# HRT.net
KiCad netlist of a schematic drawn in Altium Designer
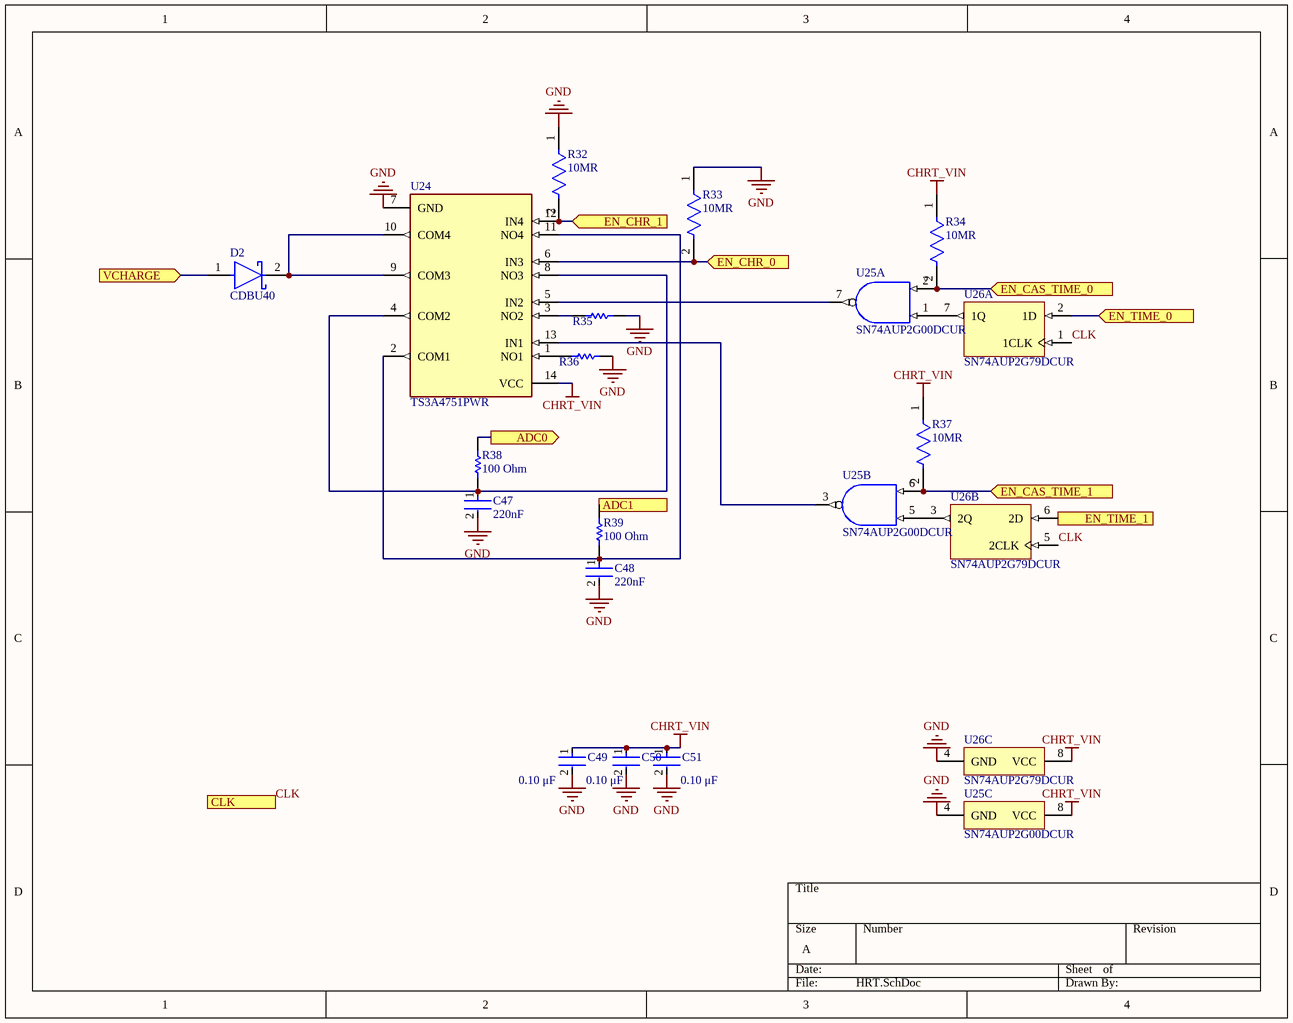
[diagram p0: HRT.SchDoc]

(export (version "E")
  (design (tool "Eeschema 10.0.6"))
  (components
    (comp (ref "C47")
      (value "GRM155R71C224KA12D")
      (footprint "FP-GRM155-0_05-IPC_C")
      (description "Chip Multilayer Ceramic Capacitors for General Purpose, 0402, 0.22uF, X7R, 15%, 10%, 16V")
      (fields
        (field (name "CAPACITANCE") "220nF")
        (field (name "VOLTAGE") "16V")
        (field (name "TOLERANCE") "10%")
      )
      (libsource (lib "Altium Content Vault") (part "02cd4be3c70576c341d710602a673aa"))
    )
    (comp (ref "C48")
      (value "GRM155R71C224KA12D")
      (footprint "FP-GRM155-0_05-IPC_C")
      (description "Chip Multilayer Ceramic Capacitors for General Purpose, 0402, 0.22uF, X7R, 15%, 10%, 16V")
      (fields
        (field (name "CAPACITANCE") "220nF")
        (field (name "VOLTAGE") "16V")
        (field (name "TOLERANCE") "10%")
      )
      (libsource (lib "Altium Content Vault") (part "02cd4be3c70576c341d710602a673aa"))
    )
    (comp (ref "C49")
      (value "C0402C104K8PACTU")
      (footprint "FP-C0402-BB-MFG")
      (description "CAP CER 0.1UF 10V X5R 0402")
      (fields
        (field (name "CAPACITANCE") "0.10 μF")
        (field (name "MANUFACTURER") "Kemet")
        (field (name "TOLERANCE") "0.1")
      )
      (libsource (lib "Altium Content Vault") (part "b4654b650e69147ec39a6b967a45e02"))
    )
    (comp (ref "C50")
      (value "C0402C104K8PACTU")
      (footprint "FP-C0402-BB-MFG")
      (description "CAP CER 0.1UF 10V X5R 0402")
      (fields
        (field (name "CAPACITANCE") "0.10 μF")
        (field (name "MANUFACTURER") "Kemet")
        (field (name "TOLERANCE") "0.1")
      )
      (libsource (lib "Altium Content Vault") (part "b4654b650e69147ec39a6b967a45e02"))
    )
    (comp (ref "C51")
      (value "C0402C104K8PACTU")
      (footprint "FP-C0402-BB-MFG")
      (description "CAP CER 0.1UF 10V X5R 0402")
      (fields
        (field (name "CAPACITANCE") "0.10 μF")
        (field (name "MANUFACTURER") "Kemet")
        (field (name "TOLERANCE") "0.1")
      )
      (libsource (lib "Altium Content Vault") (part "b4654b650e69147ec39a6b967a45e02"))
    )
    (comp (ref "D2")
      (value "CDBU40")
      (footprint "FP-S8-V-3880_02-001-MFG")
      (description "DIODE SCHOTTKY 40V 120MA SOD523")
      (fields
        (field (name "OCTOPART") "https://octopart.com/bas40-02v-v-g-08-vishay-44351221")
        (field (name "MANUFACTURER") "Vishay")
      )
      (libsource (lib "Altium Content Vault") (part "360ad2f4ac25a952324d13796385471"))
    )
    (comp (ref "R32")
      (value "CRCW040210M0JNED")
      (footprint "FP-CRCW0402-e3-IPC_C")
      (description "RES Thick Film, 10MΩ, 5%, 0.063W, 200ppm/°C, 0402")
      (fields (field (name "TOLERANCE") "5%") (field (name "RESISTANCE") "10MR"))
      (libsource (lib "Altium Content Vault") (part "1029c3af85768c4190bb7ad29bc67b5"))
    )
    (comp (ref "R33")
      (value "CRCW040210M0JNED")
      (footprint "FP-CRCW0402-e3-IPC_C")
      (description "RES Thick Film, 10MΩ, 5%, 0.063W, 200ppm/°C, 0402")
      (fields (field (name "TOLERANCE") "5%") (field (name "RESISTANCE") "10MR"))
      (libsource (lib "Altium Content Vault") (part "1029c3af85768c4190bb7ad29bc67b5"))
    )
    (comp (ref "R34")
      (value "CRCW040210M0JNED")
      (footprint "FP-CRCW0402-e3-IPC_C")
      (description "RES Thick Film, 10MΩ, 5%, 0.063W, 200ppm/°C, 0402")
      (fields (field (name "TOLERANCE") "5%") (field (name "RESISTANCE") "10MR"))
      (libsource (lib "Altium Content Vault") (part "1029c3af85768c4190bb7ad29bc67b5"))
    )
    (comp (ref "R35")
      (value "CRCW040222R0FKED")
      (footprint "RESC1005X40X25LL05T05")
      (fields (field (name "MANUFACTURER") "Vishay Dale"))
      (libsource (lib "Altium Content Vault") (part "RES"))
    )
    (comp (ref "R36")
      (value "CRCW040222R0FKED")
      (footprint "RESC1005X40X25LL05T05")
      (fields (field (name "MANUFACTURER") "Vishay Dale"))
      (libsource (lib "Altium Content Vault") (part "RES"))
    )
    (comp (ref "R37")
      (value "CRCW040210M0JNED")
      (footprint "FP-CRCW0402-e3-IPC_C")
      (description "RES Thick Film, 10MΩ, 5%, 0.063W, 200ppm/°C, 0402")
      (fields (field (name "TOLERANCE") "5%") (field (name "RESISTANCE") "10MR"))
      (libsource (lib "Altium Content Vault") (part "1029c3af85768c4190bb7ad29bc67b5"))
    )
    (comp (ref "R38")
      (value "ERJ-2RKF1000X")
      (footprint "RESC1005X40X25LL05T05")
      (description "Chip Resistor, 100 Ohm, +/- 1%, 100 mW, -55 to 155 degC, 0402 (1005 Metric), RoHS, Tape and Reel")
      (fields
        (field (name "MANUFACTURER") "Basic Passives")
        (field (name "TOLERANCE") "1%")
        (field (name "RESISTANCE") "100 Ohm")
      )
      (libsource (lib "Altium Content Vault") (part "RES-2"))
    )
    (comp (ref "R39")
      (value "ERJ-2RKF1000X")
      (footprint "RESC1005X40X25LL05T05")
      (description "Chip Resistor, 100 Ohm, +/- 1%, 100 mW, -55 to 155 degC, 0402 (1005 Metric), RoHS, Tape and Reel")
      (fields
        (field (name "MANUFACTURER") "Basic Passives")
        (field (name "TOLERANCE") "1%")
        (field (name "RESISTANCE") "100 Ohm")
      )
      (libsource (lib "Altium Content Vault") (part "RES-2"))
    )
    (comp (ref "U24")
      (value "TS3A4751PWR")
      (footprint "FP-PW0014A-IPC_C")
      (description "IC SWITCH QUAD SPST 14TSSOP")
      (libsource (lib "Altium Content Vault") (part "75fdcfb842d41a92b92a478e82e68ae"))
    )
    (comp (ref "U25")
      (value "SN74AUP2G00DCUR")
      (footprint "DCU0008A_L")
      (description "Low-Power Dual 2-Input Positive-NAND Gate, DCU0008A, LARGE T&R")
      (fields
        (field (name "GENERIC PART NUMBER") "SN74AUP2G00")
        (field (name "MANUFACTURER") "Texas Instruments")
      )
      (libsource (lib "Altium Content Vault") (part "TI-SN74XXX2GXXX-8"))
    )
    (comp (ref "U26")
      (value "SN74AUP2G79DCUR")
      (footprint "DCU0008A_L")
      (description "Low-Power Dual Positive-Edge-Triggered D-Type Flip-Flop, DCU0008A, LARGE T&R")
      (fields
        (field (name "MANUFACTURER") "Texas Instruments")
        (field (name "GENERIC PART NUMBER") "SN74AUP2G79")
      )
      (libsource (lib "Altium Content Vault") (part "TI-SN74XXX2G79-8_A"))
    )
  )
  (nets
    (net (code "1") (name "/ADC0") (class "Default")
      (node (ref "R38") (pin "2") (pinfunction "2_2") (pintype "passive"))
    )
    (net (code "2") (name "/ADC1") (class "Default")
      (node (ref "R39") (pin "2") (pinfunction "2_2") (pintype "passive"))
    )
    (net (code "3") (name "/CLK") (class "Default")
      (node (ref "U26") (pin "1") (pinfunction "1CLK_1") (pintype "input"))
      (node (ref "U26") (pin "5") (pinfunction "2CLK_5") (pintype "input"))
    )
    (net (code "4") (name "/EN_CAS_TIME_0") (class "Default")
      (node (ref "R34") (pin "2") (pinfunction "2_2") (pintype "passive"))
      (node (ref "U25") (pin "2") (pinfunction "1B_2") (pintype "input"))
    )
    (net (code "5") (name "/EN_CAS_TIME_1") (class "Default")
      (node (ref "R37") (pin "2") (pinfunction "2_2") (pintype "passive"))
      (node (ref "U25") (pin "6") (pinfunction "2B_6") (pintype "input"))
    )
    (net (code "6") (name "/EN_CHR_0") (class "Default")
      (node (ref "R33") (pin "2") (pinfunction "2_2") (pintype "passive"))
      (node (ref "U24") (pin "6") (pinfunction "IN3_6") (pintype "input"))
    )
    (net (code "7") (name "/EN_CHR_1") (class "Default")
      (node (ref "R32") (pin "2") (pinfunction "2_2") (pintype "passive"))
      (node (ref "U24") (pin "12") (pinfunction "IN4_12") (pintype "input"))
    )
    (net (code "8") (name "/EN_TIME_0") (class "Default")
      (node (ref "U26") (pin "2") (pinfunction "1D_2") (pintype "input"))
    )
    (net (code "9") (name "/EN_TIME_1") (class "Default")
      (node (ref "U26") (pin "6") (pinfunction "2D_6") (pintype "input"))
    )
    (net (code "10") (name "/VCHARGE") (class "Default")
      (node (ref "D2") (pin "1") (pinfunction "A_1") (pintype "passive"))
    )
    (net (code "11") (name "CHRT_VIN") (class "Default")
      (node (ref "C49") (pin "1") (pinfunction "1_1") (pintype "passive"))
      (node (ref "C50") (pin "1") (pinfunction "1_1") (pintype "passive"))
      (node (ref "C51") (pin "1") (pinfunction "1_1") (pintype "passive"))
      (node (ref "R34") (pin "1") (pinfunction "1_1") (pintype "passive"))
      (node (ref "R37") (pin "1") (pinfunction "1_1") (pintype "passive"))
      (node (ref "U24") (pin "14") (pinfunction "VCC_14") (pintype "power_in"))
      (node (ref "U25") (pin "8") (pinfunction "VCC_8") (pintype "power_in"))
      (node (ref "U26") (pin "8") (pinfunction "VCC_8") (pintype "power_in"))
    )
    (net (code "12") (name "GND") (class "Default")
      (node (ref "C47") (pin "2") (pinfunction "2_2") (pintype "passive"))
      (node (ref "C48") (pin "2") (pinfunction "2_2") (pintype "passive"))
      (node (ref "C49") (pin "2") (pinfunction "2_2") (pintype "passive"))
      (node (ref "C50") (pin "2") (pinfunction "2_2") (pintype "passive"))
      (node (ref "C51") (pin "2") (pinfunction "2_2") (pintype "passive"))
      (node (ref "R32") (pin "1") (pinfunction "1_1") (pintype "passive"))
      (node (ref "R33") (pin "1") (pinfunction "1_1") (pintype "passive"))
      (node (ref "R35") (pin "2") (pinfunction "2_2") (pintype "passive"))
      (node (ref "R36") (pin "2") (pinfunction "2_2") (pintype "passive"))
      (node (ref "U24") (pin "7") (pinfunction "GND_7") (pintype "power_in"))
      (node (ref "U25") (pin "4") (pinfunction "GND_4") (pintype "power_in"))
      (node (ref "U26") (pin "4") (pinfunction "GND_4") (pintype "power_in"))
    )
    (net (code "13") (name "Net-(D2-C)") (class "Default")
      (node (ref "D2") (pin "2") (pinfunction "C_2") (pintype "passive"))
      (node (ref "U24") (pin "10") (pinfunction "COM4_10") (pintype "output"))
      (node (ref "U24") (pin "9") (pinfunction "COM3_9") (pintype "output"))
    )
    (net (code "14") (name "Net-(U24-COM1)") (class "Default")
      (node (ref "C48") (pin "1") (pinfunction "1_1") (pintype "passive"))
      (node (ref "R39") (pin "1") (pinfunction "1_1") (pintype "passive"))
      (node (ref "U24") (pin "11") (pinfunction "NO4_11") (pintype "input"))
      (node (ref "U24") (pin "2") (pinfunction "COM1_2") (pintype "output"))
    )
    (net (code "15") (name "Net-(U24-COM2)") (class "Default")
      (node (ref "C47") (pin "1") (pinfunction "1_1") (pintype "passive"))
      (node (ref "R38") (pin "1") (pinfunction "1_1") (pintype "passive"))
      (node (ref "U24") (pin "4") (pinfunction "COM2_4") (pintype "output"))
      (node (ref "U24") (pin "8") (pinfunction "NO3_8") (pintype "input"))
    )
    (net (code "16") (name "Net-(U24-IN1)") (class "Default")
      (node (ref "U24") (pin "13") (pinfunction "IN1_13") (pintype "input"))
      (node (ref "U25") (pin "3") (pinfunction "2Y_3") (pintype "output"))
    )
    (net (code "17") (name "Net-(U24-IN2)") (class "Default")
      (node (ref "U24") (pin "5") (pinfunction "IN2_5") (pintype "input"))
      (node (ref "U25") (pin "7") (pinfunction "1Y_7") (pintype "output"))
    )
    (net (code "18") (name "Net-(U24-NO1)") (class "Default")
      (node (ref "R36") (pin "1") (pinfunction "1_1") (pintype "passive"))
      (node (ref "U24") (pin "1") (pinfunction "NO1_1") (pintype "input"))
    )
    (net (code "19") (name "Net-(U24-NO2)") (class "Default")
      (node (ref "R35") (pin "1") (pinfunction "1_1") (pintype "passive"))
      (node (ref "U24") (pin "3") (pinfunction "NO2_3") (pintype "input"))
    )
    (net (code "20") (name "Net-(U25A-1A)") (class "Default")
      (node (ref "U25") (pin "1") (pinfunction "1A_1") (pintype "input"))
      (node (ref "U26") (pin "7") (pinfunction "1Q_7") (pintype "output"))
    )
    (net (code "21") (name "Net-(U25B-2A)") (class "Default")
      (node (ref "U25") (pin "5") (pinfunction "2A_5") (pintype "input"))
      (node (ref "U26") (pin "3") (pinfunction "2Q_3") (pintype "output"))
    )
  )
)
